# Motor-E.net
KiCad netlist of a schematic drawn in Altium Designer
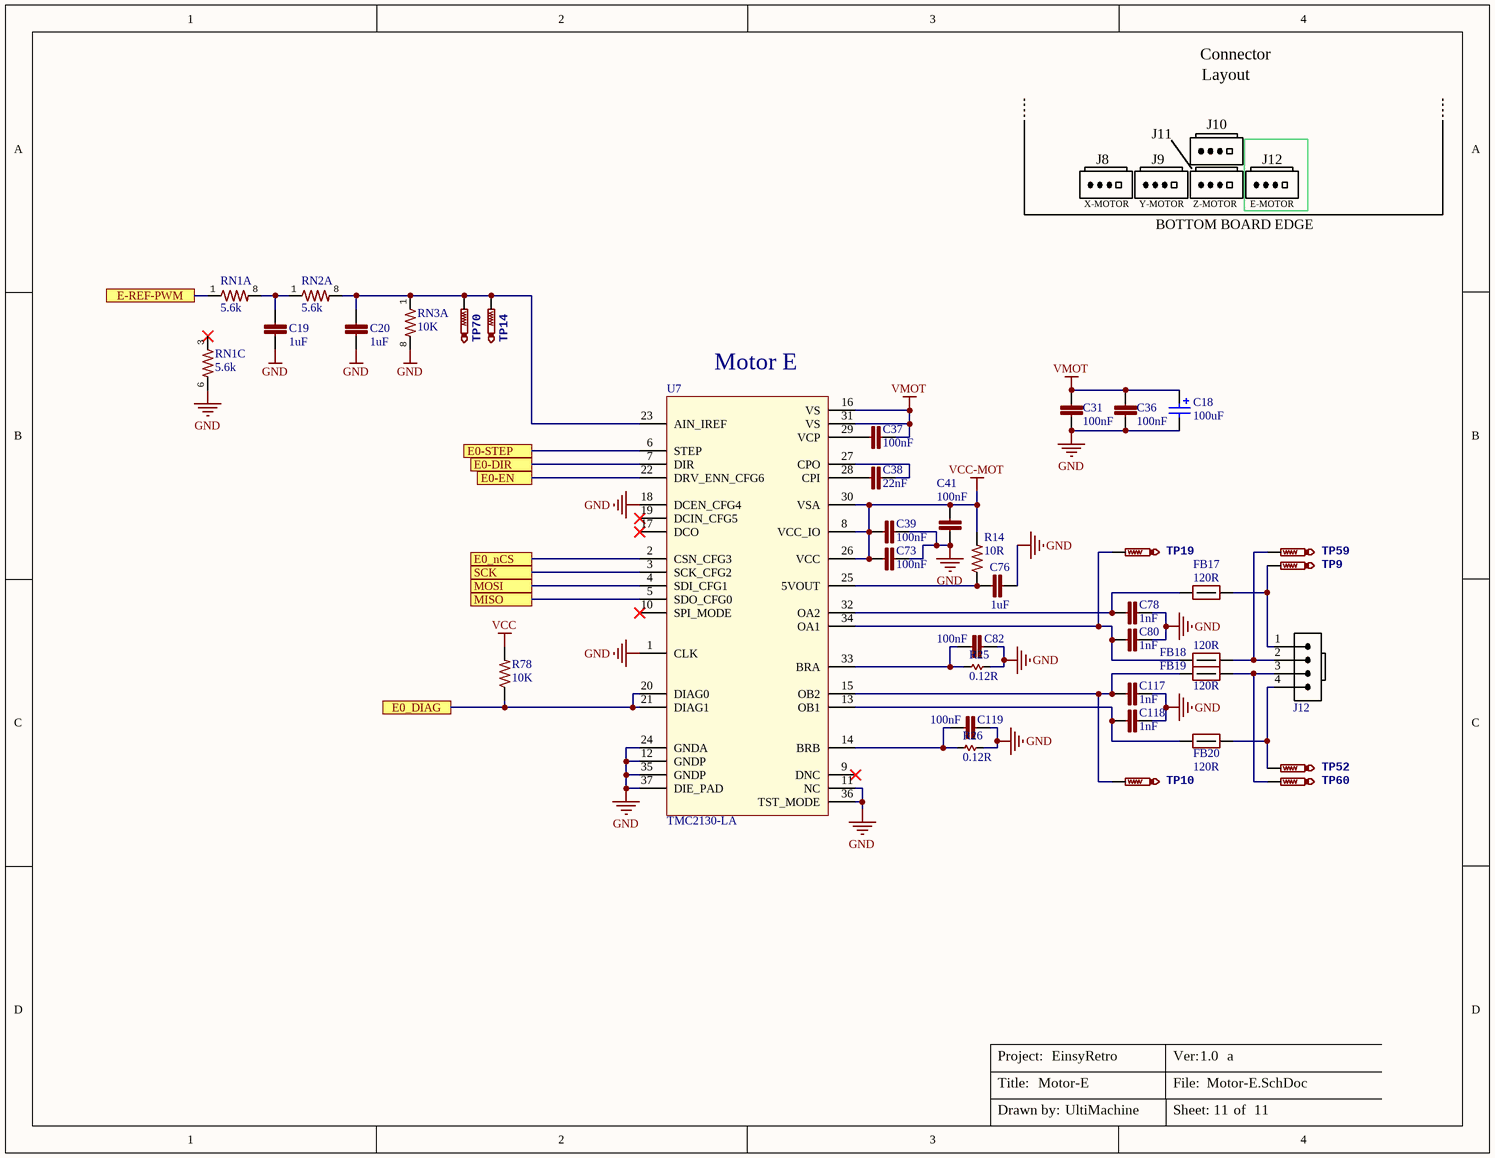
[diagram p0: Motor-E.SchDoc]

(export (version "E")
  (design (tool "Eeschema 10.0.6"))
  (components
    (comp (ref "C18")
      (value "100uF")
      (footprint "CAP-ELEC-063063077")
      (description "CAP ALUM 100UF 35V 20% SMD")
      (fields (field (name "MANUFACTURER") "Nichicon") (field (name "TOLERANCE") "+/- 20%"))
      (libsource (lib "3Delight") (part "UWT1V101MCL1GS"))
    )
    (comp (ref "C19")
      (value "1uF")
      (footprint "C0402")
      (description "CAP CER 0402 1uF 6.3V 10% X5R")
      (fields (field (name "MANUFACTURER") "Murata") (field (name "TOLERANCE") "+/- 10%"))
      (libsource (lib "3Delight") (part "GRM155R60J105KE19D"))
    )
    (comp (ref "C20")
      (value "1uF")
      (footprint "C0402")
      (description "CAP CER 0402 1uF 6.3V 10% X5R")
      (fields (field (name "MANUFACTURER") "Murata") (field (name "TOLERANCE") "+/- 10%"))
      (libsource (lib "3Delight") (part "GRM155R60J105KE19D"))
    )
    (comp (ref "C31")
      (value "100nF")
      (footprint "C0603")
      (description "CAP CER 0603 100nF 50V 10% X7R")
      (fields (field (name "MANUFACTURER") "Kemet") (field (name "TOLERANCE") "+/- 10%"))
      (libsource (lib "3Delight") (part "C0603C104K5RACTU"))
    )
    (comp (ref "C36")
      (value "100nF")
      (footprint "C0603")
      (description "CAP CER 0603 100nF 50V 10% X7R")
      (fields (field (name "MANUFACTURER") "Kemet") (field (name "TOLERANCE") "+/- 10%"))
      (libsource (lib "3Delight") (part "C0603C104K5RACTU"))
    )
    (comp (ref "C37")
      (value "100nF")
      (footprint "C0603")
      (description "CAP CER 0603 100nF 50V 10% X7R")
      (fields (field (name "MANUFACTURER") "Kemet") (field (name "TOLERANCE") "+/- 10%"))
      (libsource (lib "") (part "C0603C104K5RACTU_2"))
    )
    (comp (ref "C38")
      (value "22nF")
      (footprint "C0402")
      (description "CAP CER 0402 22nF ±10% 50V X7R")
      (fields (field (name "MANUFACTURER") "YAGEO") (field (name "TOLERANCE") "+/- 10%"))
      (libsource (lib "3Delight") (part "GCM155R71H223KA55D"))
    )
    (comp (ref "C39")
      (value "100nF")
      (footprint "C0402")
      (description "CAP CER 0402 100nF 16V 10% X7R")
      (fields (field (name "MANUFACTURER") "Murata") (field (name "TOLERANCE") "+/- 10%"))
      (libsource (lib "") (part "GRM155R71C104KA88D_1"))
    )
    (comp (ref "C41")
      (value "100nF")
      (footprint "C0402")
      (description "CAP CER 0402 100nF 16V 10% X7R")
      (fields (field (name "MANUFACTURER") "Murata") (field (name "TOLERANCE") "+/- 10%"))
      (libsource (lib "3Delight") (part "GRM155R71C104KA88D"))
    )
    (comp (ref "C73")
      (value "100nF")
      (footprint "C0402")
      (description "CAP CER 0402 100nF 16V 10% X7R")
      (fields (field (name "MANUFACTURER") "Murata") (field (name "TOLERANCE") "+/- 10%"))
      (libsource (lib "") (part "GRM155R71C104KA88D_1"))
    )
    (comp (ref "C76")
      (value "1uF")
      (footprint "C0402")
      (description "CAP CER 0402 1uF 6.3V 10% X5R")
      (fields (field (name "MANUFACTURER") "Murata") (field (name "TOLERANCE") "+/- 10%"))
      (libsource (lib "") (part "GRM155R60J105KE19D_1"))
    )
    (comp (ref "C78")
      (value "1nF")
      (footprint "C0603")
      (description "CAP CER 0603  1nF 50v 10% X7R")
      (fields (field (name "MANUFACTURER") "Kemet") (field (name "TOLERANCE") "+/- 10%"))
      (libsource (lib "3Delight") (part "C0603C102K5RACTU"))
    )
    (comp (ref "C80")
      (value "1nF")
      (footprint "C0603")
      (description "CAP CER 0603  1nF 50v 10% X7R")
      (fields (field (name "MANUFACTURER") "Kemet") (field (name "TOLERANCE") "+/- 10%"))
      (libsource (lib "3Delight") (part "C0603C102K5RACTU"))
    )
    (comp (ref "C82")
      (value "100nF")
      (footprint "C0603")
      (description "CAP CER 0603 100nF 50V 10% X7R")
      (fields (field (name "MANUFACTURER") "Kemet") (field (name "TOLERANCE") "+/- 10%"))
      (libsource (lib "") (part "C0603C104K5RACTU_1"))
    )
    (comp (ref "C117")
      (value "1nF")
      (footprint "C0603")
      (description "CAP CER 0603  1nF 50v 10% X7R")
      (fields (field (name "MANUFACTURER") "Kemet") (field (name "TOLERANCE") "+/- 10%"))
      (libsource (lib "3Delight") (part "C0603C102K5RACTU"))
    )
    (comp (ref "C118")
      (value "1nF")
      (footprint "C0603")
      (description "CAP CER 0603  1nF 50v 10% X7R")
      (fields (field (name "MANUFACTURER") "Kemet") (field (name "TOLERANCE") "+/- 10%"))
      (libsource (lib "3Delight") (part "C0603C102K5RACTU"))
    )
    (comp (ref "C119")
      (value "100nF")
      (footprint "C0603")
      (description "CAP CER 0603 100nF 50V 10% X7R")
      (fields (field (name "MANUFACTURER") "Kemet") (field (name "TOLERANCE") "+/- 10%"))
      (libsource (lib "") (part "C0603C104K5RACTU_1"))
    )
    (comp (ref "FB17")
      (value "120R")
      (footprint "FB0603")
      (description "FERRITE BEAD 120 OHM 0603 1LN")
      (fields (field (name "MANUFACTURER") "Samsung") (field (name "PART") "FERRITE 120R 3A 0603"))
      (libsource (lib "Inductors") (part "FERRITE 120R 3A 0603"))
    )
    (comp (ref "FB18")
      (value "120R")
      (footprint "FB0603")
      (description "FERRITE BEAD 120 OHM 0603 1LN")
      (fields (field (name "MANUFACTURER") "Samsung") (field (name "PART") "FERRITE 120R 3A 0603"))
      (libsource (lib "Inductors") (part "FERRITE 120R 3A 0603"))
    )
    (comp (ref "FB19")
      (value "120R")
      (footprint "FB0603")
      (description "FERRITE BEAD 120 OHM 0603 1LN")
      (fields (field (name "MANUFACTURER") "Samsung") (field (name "PART") "FERRITE 120R 3A 0603"))
      (libsource (lib "Inductors") (part "FERRITE 120R 3A 0603"))
    )
    (comp (ref "FB20")
      (value "120R")
      (footprint "FB0603")
      (description "FERRITE BEAD 120 OHM 0603 1LN")
      (fields (field (name "MANUFACTURER") "Samsung") (field (name "PART") "FERRITE 120R 3A 0603"))
      (libsource (lib "Inductors") (part "FERRITE 120R 3A 0603"))
    )
    (comp (ref "J12")
      (value "Molex 0705430003")
      (footprint "4POL254 PIN-IN-PASTE")
      (description "Molex 4 Pin Clip Connector - Pin In Paste footprint")
      (libsource (lib "Connectors") (part "Molex 0705430003 PIP"))
    )
    (comp (ref "R14")
      (value "10R")
      (footprint "R0402")
      (description "RES SMD 10 OHM 1% 1/16W 0402")
      (fields (field (name "MANUFACTURER") "Yageo") (field (name "TOLERANCE") "+/- 1%"))
      (libsource (lib "3Delight") (part "RC0402FR-0710RL"))
    )
    (comp (ref "R25")
      (value "0.12R")
      (footprint "R1206")
      (description "RES 0.12 OHM 1% 1/2W 1206")
      (fields (field (name "TOLERANCE") "+/- 1%"))
      (libsource (lib "Resistors") (part "0.12R 1% 1206"))
    )
    (comp (ref "R26")
      (value "0.12R")
      (footprint "R1206")
      (description "RES 0.12 OHM 1% 1/2W 1206")
      (fields (field (name "TOLERANCE") "+/- 1%"))
      (libsource (lib "Resistors") (part "0.12R 1% 1206"))
    )
    (comp (ref "R78")
      (value "10K")
      (footprint "R0402")
      (description "RES SMD 10K OHM 1% 1/16W 0402")
      (fields (field (name "MANUFACTURER") "Yageo") (field (name "PART") "10k 1% 0402"))
      (libsource (lib "3Delight") (part "RC0402FR-0710KP"))
    )
    (comp (ref "RN1")
      (value "5.6k")
      (footprint "CAY16")
      (description "RES ARRAY 4 RES 5.6K OHM 1206")
      (fields (field (name "MANUFACTURER") "Bourns") (field (name "TOLERANCE") "+/- 5%"))
      (libsource (lib "Resistors") (part "5.6k x 4 5% 1206"))
    )
    (comp (ref "RN2")
      (value "5.6k")
      (footprint "CAY16")
      (description "RES ARRAY 4 RES 5.6K OHM 1206")
      (fields (field (name "MANUFACTURER") "Bourns") (field (name "TOLERANCE") "+/- 5%"))
      (libsource (lib "Resistors") (part "5.6k x 4 5% 1206"))
    )
    (comp (ref "RN3")
      (value "10K")
      (footprint "CAY16")
      (description "RES ARRAY 4 RES 10K 1206 62.5mW 5%")
      (fields (field (name "MANUFACTURER") "Bourns") (field (name "TOLERANCE") "+/- 5%"))
      (libsource (lib "3Delight") (part "CAY16-103J4LF"))
    )
    (comp (ref "TP9")
      (value "TestPoint")
      (footprint "TP1-27")
      (description "Test Point")
      (libsource (lib "") (part "TestPoint_1"))
    )
    (comp (ref "TP10")
      (value "TestPoint")
      (footprint "TP1-27")
      (description "Test Point")
      (libsource (lib "") (part "TestPoint_1"))
    )
    (comp (ref "TP14")
      (value "TestPoint")
      (footprint "TP1-27")
      (description "Test Point")
      (libsource (lib "3Delight") (part "TestPoint"))
    )
    (comp (ref "TP19")
      (value "TestPoint")
      (footprint "TP1-27")
      (description "Test Point")
      (libsource (lib "") (part "TestPoint_1"))
    )
    (comp (ref "TP52")
      (value "TestPoint")
      (footprint "TP1-27")
      (description "Test Point")
      (libsource (lib "") (part "TestPoint_1"))
    )
    (comp (ref "TP59")
      (value "TestPoint")
      (footprint "TP1-27")
      (description "Test Point")
      (libsource (lib "") (part "TestPoint_1"))
    )
    (comp (ref "TP60")
      (value "TestPoint")
      (footprint "TP1-27")
      (description "Test Point")
      (libsource (lib "") (part "TestPoint_1"))
    )
    (comp (ref "TP70")
      (value "TestPoint")
      (footprint "TP1-27")
      (description "Test Point")
      (libsource (lib "3Delight") (part "TestPoint"))
    )
    (comp (ref "U7")
      (value "TMC2130-LA")
      (footprint "QFN36-50P500X600X900_HS-37N")
      (description "IC STEPPER MOTOR DVR SPI 36QFN")
      (fields (field (name "MANUFACTURER") "Trinamic") (field (name "PART") "TMC2130"))
      (libsource (lib "3Delight") (part "TMC2130-LA-T"))
    )
  )
  (nets
    (net (code "1") (name "/E-REF-PWM") (class "Default")
      (node (ref "RN1") (pin "1") (pinfunction "1_1") (pintype "passive"))
    )
    (net (code "2") (name "/E0-DIR") (class "Default")
      (node (ref "U7") (pin "7") (pinfunction "DIR_7") (pintype "passive"))
    )
    (net (code "3") (name "/E0-EN") (class "Default")
      (node (ref "U7") (pin "22") (pinfunction "DRV_ENN_CFG6_22") (pintype "passive"))
    )
    (net (code "4") (name "/E0-STEP") (class "Default")
      (node (ref "U7") (pin "6") (pinfunction "STEP_6") (pintype "passive"))
    )
    (net (code "5") (name "/E0_DIAG") (class "Default")
      (node (ref "R78") (pin "1") (pinfunction "1_1") (pintype "passive"))
      (node (ref "U7") (pin "20") (pinfunction "DIAG0_20") (pintype "passive"))
      (node (ref "U7") (pin "21") (pinfunction "DIAG1_21") (pintype "passive"))
    )
    (net (code "6") (name "/E0_nCS") (class "Default")
      (node (ref "U7") (pin "2") (pinfunction "CSN_CFG3_2") (pintype "passive"))
    )
    (net (code "7") (name "/MISO") (class "Default")
      (node (ref "U7") (pin "5") (pinfunction "SDO_CFG0_5") (pintype "passive"))
    )
    (net (code "8") (name "/MOSI") (class "Default")
      (node (ref "U7") (pin "4") (pinfunction "SDI_CFG1_4") (pintype "passive"))
    )
    (net (code "9") (name "/SCK") (class "Default")
      (node (ref "U7") (pin "3") (pinfunction "SCK_CFG2_3") (pintype "passive"))
    )
    (net (code "10") (name "GND") (class "Default")
      (node (ref "C117") (pin "2") (pinfunction "2_2") (pintype "passive"))
      (node (ref "C118") (pin "2") (pinfunction "2_2") (pintype "passive"))
      (node (ref "C119") (pin "1") (pinfunction "1_1") (pintype "passive"))
      (node (ref "C18") (pin "2") (pinfunction "2_2") (pintype "passive"))
      (node (ref "C19") (pin "2") (pinfunction "2_2") (pintype "passive"))
      (node (ref "C20") (pin "2") (pinfunction "2_2") (pintype "passive"))
      (node (ref "C31") (pin "1") (pinfunction "1_1") (pintype "passive"))
      (node (ref "C36") (pin "1") (pinfunction "1_1") (pintype "passive"))
      (node (ref "C39") (pin "1") (pinfunction "1_1") (pintype "passive"))
      (node (ref "C41") (pin "1") (pinfunction "1_1") (pintype "passive"))
      (node (ref "C73") (pin "1") (pinfunction "1_1") (pintype "passive"))
      (node (ref "C76") (pin "2") (pinfunction "2_2") (pintype "passive"))
      (node (ref "C78") (pin "2") (pinfunction "2_2") (pintype "passive"))
      (node (ref "C80") (pin "2") (pinfunction "2_2") (pintype "passive"))
      (node (ref "C82") (pin "1") (pinfunction "1_1") (pintype "passive"))
      (node (ref "R25") (pin "2") (pinfunction "2_2") (pintype "passive"))
      (node (ref "R26") (pin "2") (pinfunction "2_2") (pintype "passive"))
      (node (ref "RN1") (pin "6") (pinfunction "2_6") (pintype "passive"))
      (node (ref "RN3") (pin "8") (pinfunction "2_8") (pintype "passive"))
      (node (ref "U7") (pin "1") (pinfunction "CLK_1") (pintype "passive"))
      (node (ref "U7") (pin "11") (pinfunction "NC_11") (pintype "passive"))
      (node (ref "U7") (pin "12") (pinfunction "GNDP_12") (pintype "passive"))
      (node (ref "U7") (pin "18") (pinfunction "DCEN_CFG4_18") (pintype "passive"))
      (node (ref "U7") (pin "24") (pinfunction "GNDA_24") (pintype "passive"))
      (node (ref "U7") (pin "35") (pinfunction "GNDP_35") (pintype "passive"))
      (node (ref "U7") (pin "36") (pinfunction "TST_MODE_36") (pintype "passive"))
      (node (ref "U7") (pin "37") (pinfunction "DIE_PAD_37") (pintype "passive"))
    )
    (net (code "11") (name "Net-(FB17-Pad2)") (class "Default")
      (node (ref "FB17") (pin "2") (pinfunction "2_2") (pintype "passive"))
      (node (ref "J12") (pin "1") (pinfunction "1_1") (pintype "passive"))
      (node (ref "TP9") (pin "TP") (pinfunction "TP_TP") (pintype "passive"))
    )
    (net (code "12") (name "Net-(FB18-Pad2)") (class "Default")
      (node (ref "FB18") (pin "2") (pinfunction "2_2") (pintype "passive"))
      (node (ref "J12") (pin "2") (pinfunction "2_2") (pintype "passive"))
      (node (ref "TP59") (pin "TP") (pinfunction "TP_TP") (pintype "passive"))
    )
    (net (code "13") (name "Net-(FB19-Pad2)") (class "Default")
      (node (ref "FB19") (pin "2") (pinfunction "2_2") (pintype "passive"))
      (node (ref "J12") (pin "3") (pinfunction "3_3") (pintype "passive"))
      (node (ref "TP60") (pin "TP") (pinfunction "TP_TP") (pintype "passive"))
    )
    (net (code "14") (name "Net-(FB20-Pad2)") (class "Default")
      (node (ref "FB20") (pin "2") (pinfunction "2_2") (pintype "passive"))
      (node (ref "J12") (pin "4") (pinfunction "4_4") (pintype "passive"))
      (node (ref "TP52") (pin "TP") (pinfunction "TP_TP") (pintype "passive"))
    )
    (net (code "15") (name "Net-(RN1A-2)") (class "Default")
      (node (ref "C19") (pin "1") (pinfunction "1_1") (pintype "passive"))
      (node (ref "RN1") (pin "8") (pinfunction "2_8") (pintype "passive"))
      (node (ref "RN2") (pin "1") (pinfunction "1_1") (pintype "passive"))
    )
    (net (code "16") (name "Net-(RN2A-2)") (class "Default")
      (node (ref "C20") (pin "1") (pinfunction "1_1") (pintype "passive"))
      (node (ref "RN2") (pin "8") (pinfunction "2_8") (pintype "passive"))
      (node (ref "RN3") (pin "1") (pinfunction "1_1") (pintype "passive"))
      (node (ref "TP14") (pin "TP") (pinfunction "TP_TP") (pintype "passive"))
      (node (ref "TP70") (pin "TP") (pinfunction "TP_TP") (pintype "passive"))
      (node (ref "U7") (pin "23") (pinfunction "AIN_IREF_23") (pintype "passive"))
    )
    (net (code "17") (name "Net-(U7-5VOUT)") (class "Default")
      (node (ref "C76") (pin "1") (pinfunction "1_1") (pintype "passive"))
      (node (ref "R14") (pin "1") (pinfunction "1_1") (pintype "passive"))
      (node (ref "U7") (pin "25") (pinfunction "5VOUT_25") (pintype "passive"))
    )
    (net (code "18") (name "Net-(U7-BRA)") (class "Default")
      (node (ref "C82") (pin "2") (pinfunction "2_2") (pintype "passive"))
      (node (ref "R25") (pin "1") (pinfunction "1_1") (pintype "passive"))
      (node (ref "U7") (pin "33") (pinfunction "BRA_33") (pintype "passive"))
    )
    (net (code "19") (name "Net-(U7-BRB)") (class "Default")
      (node (ref "C119") (pin "2") (pinfunction "2_2") (pintype "passive"))
      (node (ref "R26") (pin "1") (pinfunction "1_1") (pintype "passive"))
      (node (ref "U7") (pin "14") (pinfunction "BRB_14") (pintype "passive"))
    )
    (net (code "20") (name "Net-(U7-CPI)") (class "Default")
      (node (ref "C38") (pin "1") (pinfunction "1_1") (pintype "passive"))
      (node (ref "U7") (pin "28") (pinfunction "CPI_28") (pintype "passive"))
    )
    (net (code "21") (name "Net-(U7-CPO)") (class "Default")
      (node (ref "C38") (pin "2") (pinfunction "2_2") (pintype "passive"))
      (node (ref "U7") (pin "27") (pinfunction "CPO_27") (pintype "passive"))
    )
    (net (code "22") (name "Net-(U7-OA1)") (class "Default")
      (node (ref "C80") (pin "1") (pinfunction "1_1") (pintype "passive"))
      (node (ref "FB18") (pin "1") (pinfunction "1_1") (pintype "passive"))
      (node (ref "TP19") (pin "TP") (pinfunction "TP_TP") (pintype "passive"))
      (node (ref "U7") (pin "34") (pinfunction "OA1_34") (pintype "passive"))
    )
    (net (code "23") (name "Net-(U7-OA2)") (class "Default")
      (node (ref "C78") (pin "1") (pinfunction "1_1") (pintype "passive"))
      (node (ref "FB17") (pin "1") (pinfunction "1_1") (pintype "passive"))
      (node (ref "U7") (pin "32") (pinfunction "OA2_32") (pintype "passive"))
    )
    (net (code "24") (name "Net-(U7-OB1)") (class "Default")
      (node (ref "C118") (pin "1") (pinfunction "1_1") (pintype "passive"))
      (node (ref "FB20") (pin "1") (pinfunction "1_1") (pintype "passive"))
      (node (ref "U7") (pin "13") (pinfunction "OB1_13") (pintype "passive"))
    )
    (net (code "25") (name "Net-(U7-OB2)") (class "Default")
      (node (ref "C117") (pin "1") (pinfunction "1_1") (pintype "passive"))
      (node (ref "FB19") (pin "1") (pinfunction "1_1") (pintype "passive"))
      (node (ref "TP10") (pin "TP") (pinfunction "TP_TP") (pintype "passive"))
      (node (ref "U7") (pin "15") (pinfunction "OB2_15") (pintype "passive"))
    )
    (net (code "26") (name "Net-(U7-VCP)") (class "Default")
      (node (ref "C37") (pin "1") (pinfunction "1_1") (pintype "passive"))
      (node (ref "U7") (pin "29") (pinfunction "VCP_29") (pintype "passive"))
    )
    (net (code "27") (name "VCC") (class "Default")
      (node (ref "R78") (pin "2") (pinfunction "2_2") (pintype "passive"))
    )
    (net (code "28") (name "VCC-MOT") (class "Default")
      (node (ref "C39") (pin "2") (pinfunction "2_2") (pintype "passive"))
      (node (ref "C41") (pin "2") (pinfunction "2_2") (pintype "passive"))
      (node (ref "C73") (pin "2") (pinfunction "2_2") (pintype "passive"))
      (node (ref "R14") (pin "2") (pinfunction "2_2") (pintype "passive"))
      (node (ref "U7") (pin "26") (pinfunction "VCC_26") (pintype "passive"))
      (node (ref "U7") (pin "30") (pinfunction "VSA_30") (pintype "passive"))
      (node (ref "U7") (pin "8") (pinfunction "VCC_IO_8") (pintype "passive"))
    )
    (net (code "29") (name "VMOT") (class "Default")
      (node (ref "C18") (pin "1") (pinfunction "1_1") (pintype "passive"))
      (node (ref "C31") (pin "2") (pinfunction "2_2") (pintype "passive"))
      (node (ref "C36") (pin "2") (pinfunction "2_2") (pintype "passive"))
      (node (ref "C37") (pin "2") (pinfunction "2_2") (pintype "passive"))
      (node (ref "U7") (pin "16") (pinfunction "VS_16") (pintype "passive"))
      (node (ref "U7") (pin "31") (pinfunction "VS_31") (pintype "passive"))
    )
    (net (code "30") (name "unconnected-(RN1C-1-Pad3)") (class "Default")
      (node (ref "RN1") (pin "3") (pinfunction "1_3") (pintype "passive+no_connect"))
    )
    (net (code "31") (name "unconnected-(U7-DCIN_CFG5-Pad19)") (class "Default")
      (node (ref "U7") (pin "19") (pinfunction "DCIN_CFG5_19") (pintype "passive+no_connect"))
    )
    (net (code "32") (name "unconnected-(U7-DCO-Pad17)") (class "Default")
      (node (ref "U7") (pin "17") (pinfunction "DCO_17") (pintype "passive+no_connect"))
    )
    (net (code "33") (name "unconnected-(U7-DNC-Pad9)") (class "Default")
      (node (ref "U7") (pin "9") (pinfunction "DNC_9") (pintype "passive+no_connect"))
    )
    (net (code "34") (name "unconnected-(U7-SPI_MODE-Pad10)") (class "Default")
      (node (ref "U7") (pin "10") (pinfunction "SPI_MODE_10") (pintype "passive+no_connect"))
    )
  )
)
